# S7CAS-PLEIADES-CARTE-MERE_P02_FPGA_B2B3.net
KiCad netlist of a schematic drawn in Altium Designer
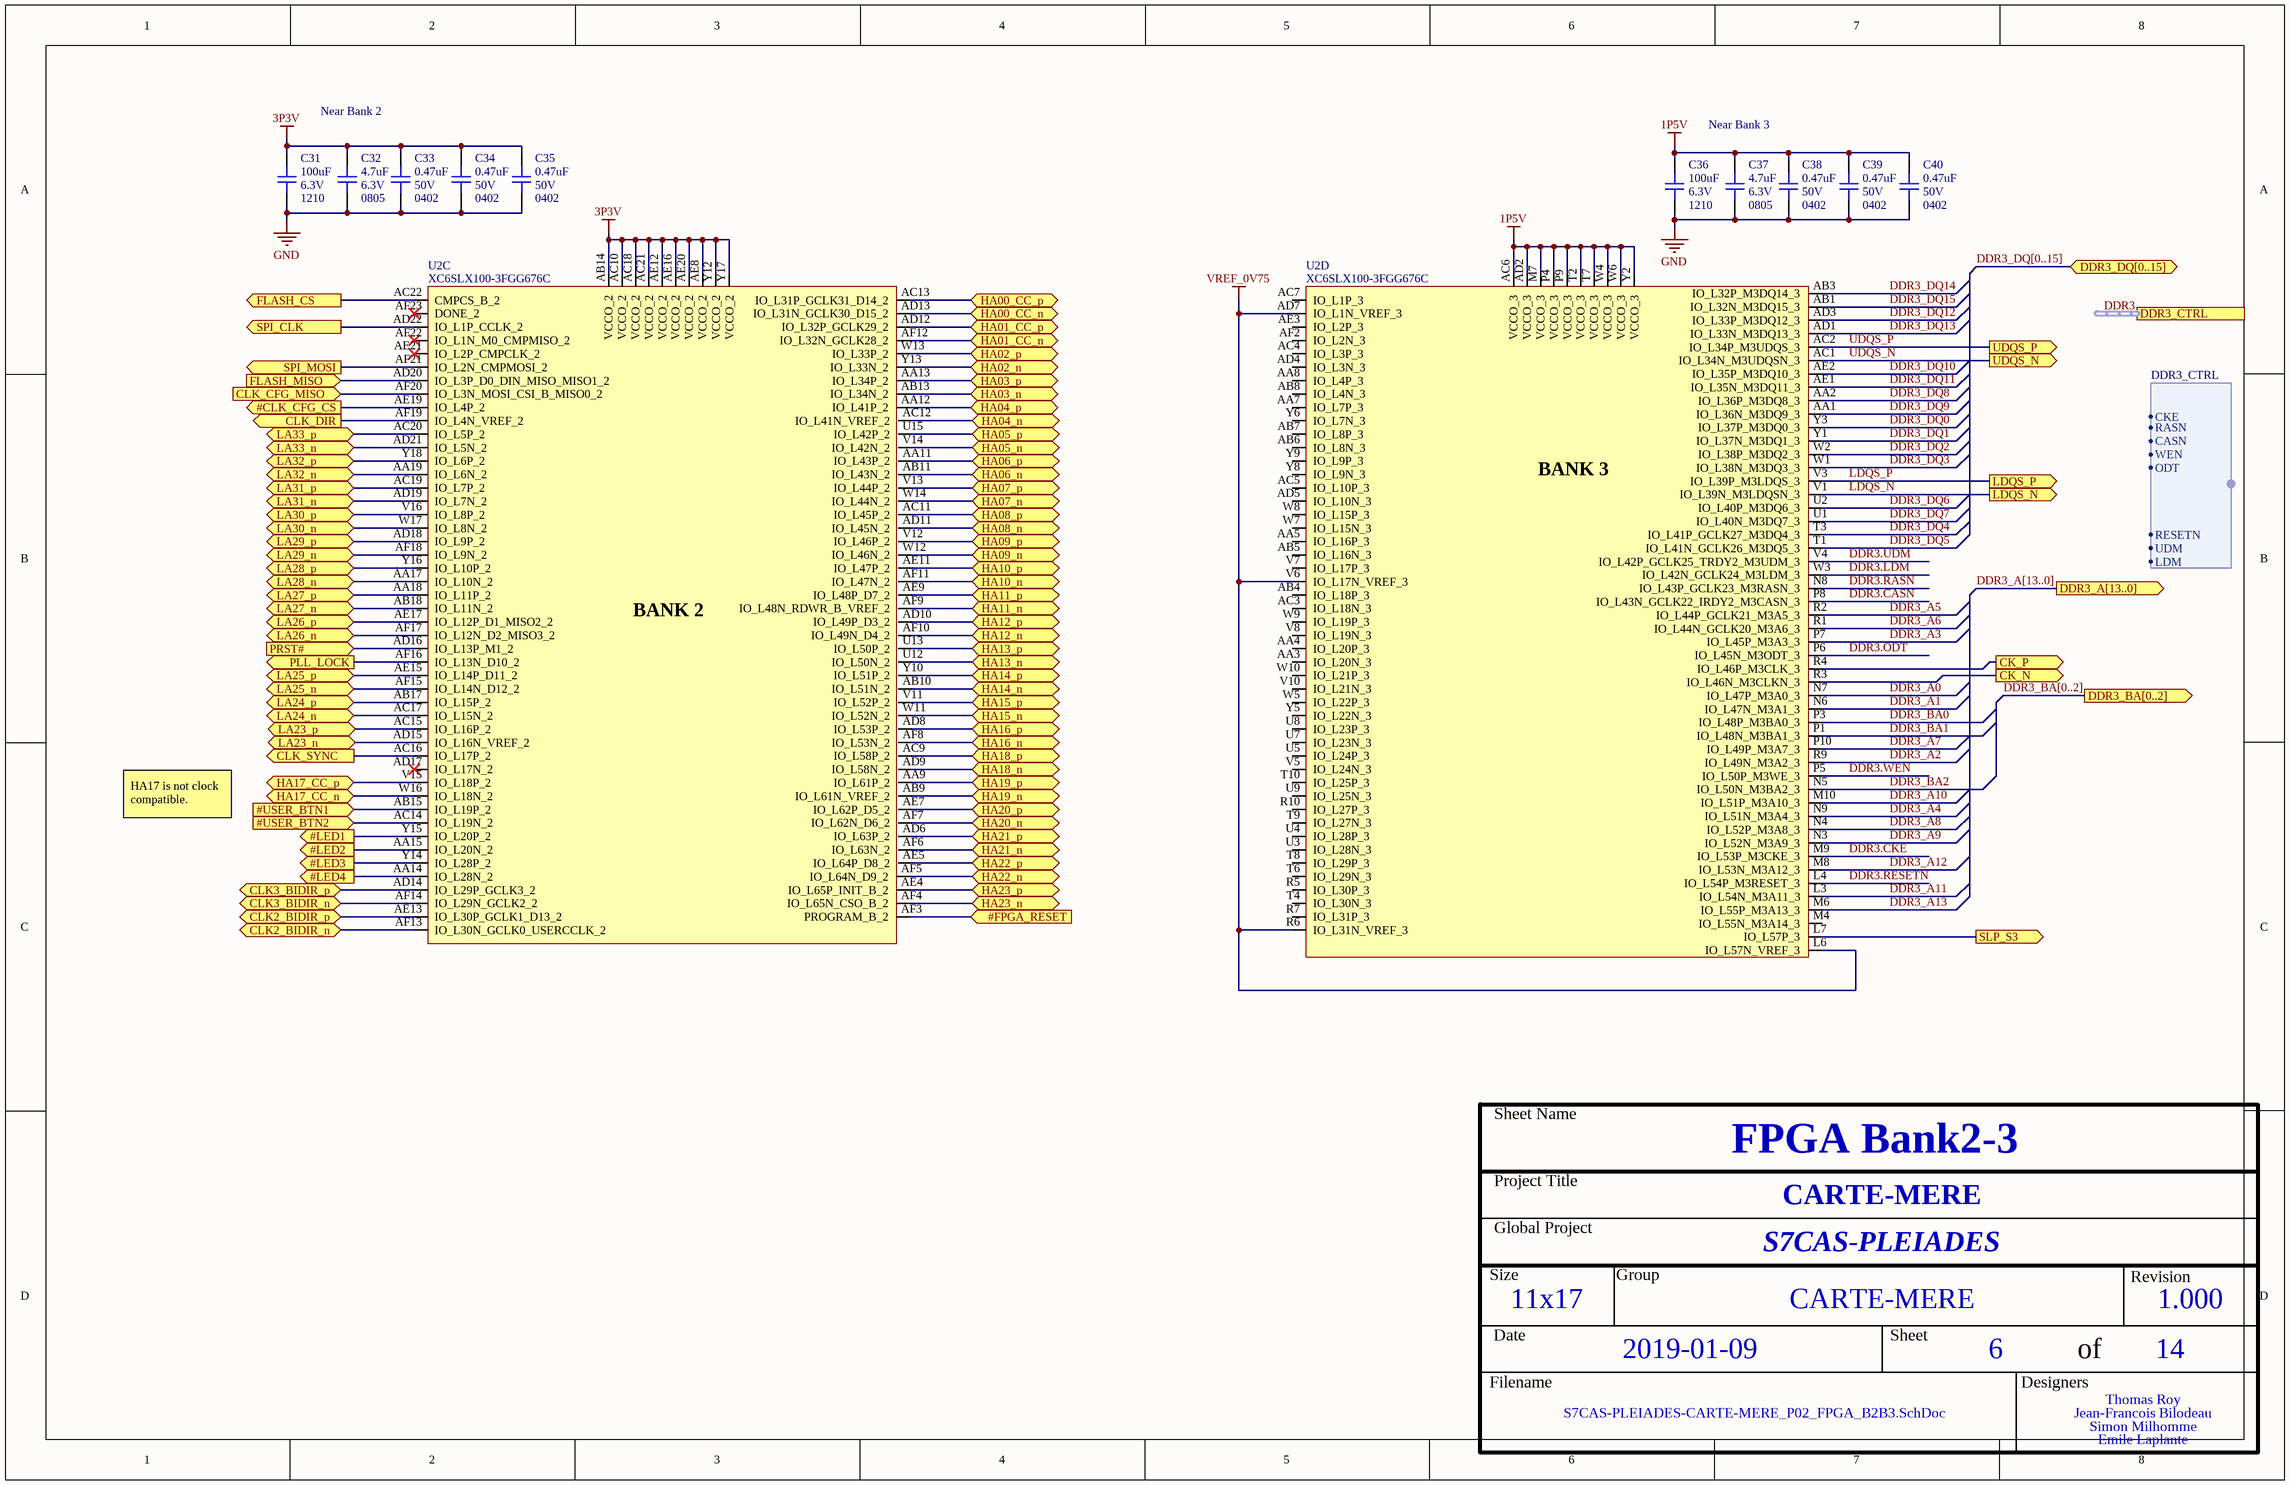
[diagram p0: S7CAS-PLEIADES-CARTE-MERE_P02_FPGA_B2B3.SchDoc]

(export (version "E")
  (design (tool "Eeschema 10.0.6"))
  (components
    (comp (ref "C31")
      (value "100uF")
      (footprint "CAP_1210")
      (description "CAP - 1210")
      (fields
        (field (name "VOLTAGE") "6.3V")
        (field (name "PACKAGE") "1210")
        (field (name "CREATEDBY") "Jonathan Bouchard")
      )
      (libsource (lib "S7CAS_Lib2019_REV1_00") (part "CAP - 1210"))
    )
    (comp (ref "C32")
      (value "4.7uF")
      (footprint "CAP_0805")
      (description "CAP - 0805")
      (fields
        (field (name "VOLTAGE") "6.3V")
        (field (name "PACKAGE") "0805")
        (field (name "CREATEDBY") "Jonathan Bouchard")
      )
      (libsource (lib "S7CAS_Lib2019_REV1_00") (part "CAP - 0805"))
    )
    (comp (ref "C33")
      (value "0.47uF")
      (footprint "CAP_0402")
      (description "CAP - 0402")
      (fields
        (field (name "VOLTAGE") "50V")
        (field (name "PACKAGE") "0402")
        (field (name "CREATEDBY") "Jonathan Bouchard")
      )
      (libsource (lib "S7CAS_Lib2019_REV1_00") (part "CAP - 0402"))
    )
    (comp (ref "C34")
      (value "0.47uF")
      (footprint "CAP_0402")
      (description "CAP - 0402")
      (fields
        (field (name "VOLTAGE") "50V")
        (field (name "PACKAGE") "0402")
        (field (name "CREATEDBY") "Jonathan Bouchard")
      )
      (libsource (lib "S7CAS_Lib2019_REV1_00") (part "CAP - 0402"))
    )
    (comp (ref "C35")
      (value "0.47uF")
      (footprint "CAP_0402")
      (description "CAP - 0402")
      (fields
        (field (name "VOLTAGE") "50V")
        (field (name "PACKAGE") "0402")
        (field (name "CREATEDBY") "Jonathan Bouchard")
      )
      (libsource (lib "S7CAS_Lib2019_REV1_00") (part "CAP - 0402"))
    )
    (comp (ref "C36")
      (value "100uF")
      (footprint "CAP_1210")
      (description "CAP - 1210")
      (fields
        (field (name "VOLTAGE") "6.3V")
        (field (name "PACKAGE") "1210")
        (field (name "CREATEDBY") "Jonathan Bouchard")
      )
      (libsource (lib "S7CAS_Lib2019_REV1_00") (part "CAP - 1210"))
    )
    (comp (ref "C37")
      (value "4.7uF")
      (footprint "CAP_0805")
      (description "CAP - 0805")
      (fields
        (field (name "VOLTAGE") "6.3V")
        (field (name "PACKAGE") "0805")
        (field (name "CREATEDBY") "Jonathan Bouchard")
      )
      (libsource (lib "S7CAS_Lib2019_REV1_00") (part "CAP - 0805"))
    )
    (comp (ref "C38")
      (value "0.47uF")
      (footprint "CAP_0402")
      (description "CAP - 0402")
      (fields
        (field (name "VOLTAGE") "50V")
        (field (name "PACKAGE") "0402")
        (field (name "CREATEDBY") "Jonathan Bouchard")
      )
      (libsource (lib "S7CAS_Lib2019_REV1_00") (part "CAP - 0402"))
    )
    (comp (ref "C39")
      (value "0.47uF")
      (footprint "CAP_0402")
      (description "CAP - 0402")
      (fields
        (field (name "VOLTAGE") "50V")
        (field (name "PACKAGE") "0402")
        (field (name "CREATEDBY") "Jonathan Bouchard")
      )
      (libsource (lib "S7CAS_Lib2019_REV1_00") (part "CAP - 0402"))
    )
    (comp (ref "C40")
      (value "0.47uF")
      (footprint "CAP_0402")
      (description "CAP - 0402")
      (fields
        (field (name "VOLTAGE") "50V")
        (field (name "PACKAGE") "0402")
        (field (name "CREATEDBY") "Jonathan Bouchard")
      )
      (libsource (lib "S7CAS_Lib2019_REV1_00") (part "CAP - 0402"))
    )
    (comp (ref "U2")
      (value "XC6SLX100-3FGG676C")
      (footprint "FPGA_XILINX_FGG676")
      (description "FPGA - XILINX SPARTAN 6 480 I/O - BGA-676")
      (fields
        (field (name "VOLTAGE") "1.14 V ~ 1.26 V")
        (field (name "MFG") "Xilinx")
        (field (name "CREATEDBY") "Jonathan Bouchard")
      )
      (libsource (lib "S7CAS_Lib2019_REV1_00") (part "FPGA_XC6SLX100-3FGG676C"))
    )
  )
  (nets
    (net (code "2") (name "/#CLK_CFG_CS") (class "Default")
      (node (ref "U2") (pin "AE19") (pinfunction "IO_L4P_2_AE19") (pintype "passive"))
    )
    (net (code "3") (name "/#FPGA_RESET") (class "Default")
      (node (ref "U2") (pin "AF3") (pinfunction "PROGRAM_B_2_AF3") (pintype "passive"))
    )
    (net (code "4") (name "/#LED1") (class "Default")
      (node (ref "U2") (pin "Y15") (pinfunction "IO_L20P_2_Y15") (pintype "passive"))
    )
    (net (code "5") (name "/#LED2") (class "Default")
      (node (ref "U2") (pin "AA15") (pinfunction "IO_L20N_2_AA15") (pintype "passive"))
    )
    (net (code "6") (name "/#LED3") (class "Default")
      (node (ref "U2") (pin "Y14") (pinfunction "IO_L28P_2_Y14") (pintype "passive"))
    )
    (net (code "7") (name "/#LED4") (class "Default")
      (node (ref "U2") (pin "AA14") (pinfunction "IO_L28N_2_AA14") (pintype "passive"))
    )
    (net (code "8") (name "/#USER_BTN1") (class "Default")
      (node (ref "U2") (pin "AB15") (pinfunction "IO_L19P_2_AB15") (pintype "passive"))
    )
    (net (code "9") (name "/#USER_BTN2") (class "Default")
      (node (ref "U2") (pin "AC14") (pinfunction "IO_L19N_2_AC14") (pintype "passive"))
    )
    (net (code "10") (name "/CK_N") (class "Default")
      (node (ref "U2") (pin "R3") (pinfunction "IO_L46N_M3CLKN_3_R3") (pintype "passive"))
    )
    (net (code "11") (name "/CK_P") (class "Default")
      (node (ref "U2") (pin "R4") (pinfunction "IO_L46P_M3CLK_3_R4") (pintype "passive"))
    )
    (net (code "12") (name "/CLK2_BIDIR_n") (class "Default")
      (node (ref "U2") (pin "AF13") (pinfunction "IO_L30N_GCLK0_USERCCLK_2_AF13") (pintype "passive"))
    )
    (net (code "13") (name "/CLK2_BIDIR_p") (class "Default")
      (node (ref "U2") (pin "AE13") (pinfunction "IO_L30P_GCLK1_D13_2_AE13") (pintype "passive"))
    )
    (net (code "14") (name "/CLK3_BIDIR_n") (class "Default")
      (node (ref "U2") (pin "AF14") (pinfunction "IO_L29N_GCLK2_2_AF14") (pintype "passive"))
    )
    (net (code "15") (name "/CLK3_BIDIR_p") (class "Default")
      (node (ref "U2") (pin "AD14") (pinfunction "IO_L29P_GCLK3_2_AD14") (pintype "passive"))
    )
    (net (code "16") (name "/CLK_CFG_MISO") (class "Default")
      (node (ref "U2") (pin "AF20") (pinfunction "IO_L3N_MOSI_CSI_B_MISO0_2_AF20") (pintype "passive"))
    )
    (net (code "17") (name "/CLK_DIR") (class "Default")
      (node (ref "U2") (pin "AF19") (pinfunction "IO_L4N_VREF_2_AF19") (pintype "passive"))
    )
    (net (code "18") (name "/CLK_SYNC") (class "Default")
      (node (ref "U2") (pin "AC16") (pinfunction "IO_L17P_2_AC16") (pintype "passive"))
    )
    (net (code "19") (name "/DDR3.CASN") (class "Default")
      (node (ref "U2") (pin "P8") (pinfunction "IO_L43N_GCLK22_IRDY2_M3CASN_3_P8") (pintype "passive"))
    )
    (net (code "20") (name "/DDR3.CKE") (class "Default")
      (node (ref "U2") (pin "M9") (pinfunction "IO_L53P_M3CKE_3_M9") (pintype "passive"))
    )
    (net (code "21") (name "/DDR3.LDM") (class "Default")
      (node (ref "U2") (pin "W3") (pinfunction "IO_L42N_GCLK24_M3LDM_3_W3") (pintype "passive"))
    )
    (net (code "22") (name "/DDR3.ODT") (class "Default")
      (node (ref "U2") (pin "P6") (pinfunction "IO_L45N_M3ODT_3_P6") (pintype "passive"))
    )
    (net (code "23") (name "/DDR3.RASN") (class "Default")
      (node (ref "U2") (pin "N8") (pinfunction "IO_L43P_GCLK23_M3RASN_3_N8") (pintype "passive"))
    )
    (net (code "24") (name "/DDR3.RESETN") (class "Default")
      (node (ref "U2") (pin "L4") (pinfunction "IO_L54P_M3RESET_3_L4") (pintype "passive"))
    )
    (net (code "25") (name "/DDR3.UDM") (class "Default")
      (node (ref "U2") (pin "V4") (pinfunction "IO_L42P_GCLK25_TRDY2_M3UDM_3_V4") (pintype "passive"))
    )
    (net (code "26") (name "/DDR3.WEN") (class "Default")
      (node (ref "U2") (pin "P5") (pinfunction "IO_L50P_M3WE_3_P5") (pintype "passive"))
    )
    (net (code "27") (name "/DDR3_A0") (class "Default")
      (node (ref "U2") (pin "N7") (pinfunction "IO_L47P_M3A0_3_N7") (pintype "passive"))
    )
    (net (code "28") (name "/DDR3_A1") (class "Default")
      (node (ref "U2") (pin "N6") (pinfunction "IO_L47N_M3A1_3_N6") (pintype "passive"))
    )
    (net (code "29") (name "/DDR3_A2") (class "Default")
      (node (ref "U2") (pin "R9") (pinfunction "IO_L49N_M3A2_3_R9") (pintype "passive"))
    )
    (net (code "30") (name "/DDR3_A3") (class "Default")
      (node (ref "U2") (pin "P7") (pinfunction "IO_L45P_M3A3_3_P7") (pintype "passive"))
    )
    (net (code "31") (name "/DDR3_A4") (class "Default")
      (node (ref "U2") (pin "N9") (pinfunction "IO_L51N_M3A4_3_N9") (pintype "passive"))
    )
    (net (code "32") (name "/DDR3_A5") (class "Default")
      (node (ref "U2") (pin "R2") (pinfunction "IO_L44P_GCLK21_M3A5_3_R2") (pintype "passive"))
    )
    (net (code "33") (name "/DDR3_A6") (class "Default")
      (node (ref "U2") (pin "R1") (pinfunction "IO_L44N_GCLK20_M3A6_3_R1") (pintype "passive"))
    )
    (net (code "34") (name "/DDR3_A7") (class "Default")
      (node (ref "U2") (pin "P10") (pinfunction "IO_L49P_M3A7_3_P10") (pintype "passive"))
    )
    (net (code "35") (name "/DDR3_A8") (class "Default")
      (node (ref "U2") (pin "N4") (pinfunction "IO_L52P_M3A8_3_N4") (pintype "passive"))
    )
    (net (code "36") (name "/DDR3_A9") (class "Default")
      (node (ref "U2") (pin "N3") (pinfunction "IO_L52N_M3A9_3_N3") (pintype "passive"))
    )
    (net (code "37") (name "/DDR3_A10") (class "Default")
      (node (ref "U2") (pin "M10") (pinfunction "IO_L51P_M3A10_3_M10") (pintype "passive"))
    )
    (net (code "38") (name "/DDR3_A11") (class "Default")
      (node (ref "U2") (pin "L3") (pinfunction "IO_L54N_M3A11_3_L3") (pintype "passive"))
    )
    (net (code "39") (name "/DDR3_A12") (class "Default")
      (node (ref "U2") (pin "M8") (pinfunction "IO_L53N_M3A12_3_M8") (pintype "passive"))
    )
    (net (code "40") (name "/DDR3_A13") (class "Default")
      (node (ref "U2") (pin "M6") (pinfunction "IO_L55P_M3A13_3_M6") (pintype "passive"))
    )
    (net (code "42") (name "/DDR3_BA0") (class "Default")
      (node (ref "U2") (pin "P3") (pinfunction "IO_L48P_M3BA0_3_P3") (pintype "passive"))
    )
    (net (code "43") (name "/DDR3_BA1") (class "Default")
      (node (ref "U2") (pin "P1") (pinfunction "IO_L48N_M3BA1_3_P1") (pintype "passive"))
    )
    (net (code "44") (name "/DDR3_BA2") (class "Default")
      (node (ref "U2") (pin "N5") (pinfunction "IO_L50N_M3BA2_3_N5") (pintype "passive"))
    )
    (net (code "46") (name "/DDR3_DQ0") (class "Default")
      (node (ref "U2") (pin "Y3") (pinfunction "IO_L37P_M3DQ0_3_Y3") (pintype "passive"))
    )
    (net (code "47") (name "/DDR3_DQ1") (class "Default")
      (node (ref "U2") (pin "Y1") (pinfunction "IO_L37N_M3DQ1_3_Y1") (pintype "passive"))
    )
    (net (code "48") (name "/DDR3_DQ2") (class "Default")
      (node (ref "U2") (pin "W2") (pinfunction "IO_L38P_M3DQ2_3_W2") (pintype "passive"))
    )
    (net (code "49") (name "/DDR3_DQ3") (class "Default")
      (node (ref "U2") (pin "W1") (pinfunction "IO_L38N_M3DQ3_3_W1") (pintype "passive"))
    )
    (net (code "50") (name "/DDR3_DQ4") (class "Default")
      (node (ref "U2") (pin "T3") (pinfunction "IO_L41P_GCLK27_M3DQ4_3_T3") (pintype "passive"))
    )
    (net (code "51") (name "/DDR3_DQ5") (class "Default")
      (node (ref "U2") (pin "T1") (pinfunction "IO_L41N_GCLK26_M3DQ5_3_T1") (pintype "passive"))
    )
    (net (code "52") (name "/DDR3_DQ6") (class "Default")
      (node (ref "U2") (pin "U2") (pinfunction "IO_L40P_M3DQ6_3_U2") (pintype "passive"))
    )
    (net (code "53") (name "/DDR3_DQ7") (class "Default")
      (node (ref "U2") (pin "U1") (pinfunction "IO_L40N_M3DQ7_3_U1") (pintype "passive"))
    )
    (net (code "54") (name "/DDR3_DQ8") (class "Default")
      (node (ref "U2") (pin "AA2") (pinfunction "IO_L36P_M3DQ8_3_AA2") (pintype "passive"))
    )
    (net (code "55") (name "/DDR3_DQ9") (class "Default")
      (node (ref "U2") (pin "AA1") (pinfunction "IO_L36N_M3DQ9_3_AA1") (pintype "passive"))
    )
    (net (code "56") (name "/DDR3_DQ10") (class "Default")
      (node (ref "U2") (pin "AE2") (pinfunction "IO_L35P_M3DQ10_3_AE2") (pintype "passive"))
    )
    (net (code "57") (name "/DDR3_DQ11") (class "Default")
      (node (ref "U2") (pin "AE1") (pinfunction "IO_L35N_M3DQ11_3_AE1") (pintype "passive"))
    )
    (net (code "58") (name "/DDR3_DQ12") (class "Default")
      (node (ref "U2") (pin "AD3") (pinfunction "IO_L33P_M3DQ12_3_AD3") (pintype "passive"))
    )
    (net (code "59") (name "/DDR3_DQ13") (class "Default")
      (node (ref "U2") (pin "AD1") (pinfunction "IO_L33N_M3DQ13_3_AD1") (pintype "passive"))
    )
    (net (code "60") (name "/DDR3_DQ14") (class "Default")
      (node (ref "U2") (pin "AB3") (pinfunction "IO_L32P_M3DQ14_3_AB3") (pintype "passive"))
    )
    (net (code "61") (name "/DDR3_DQ15") (class "Default")
      (node (ref "U2") (pin "AB1") (pinfunction "IO_L32N_M3DQ15_3_AB1") (pintype "passive"))
    )
    (net (code "63") (name "/FLASH_CS") (class "Default")
      (node (ref "U2") (pin "AC22") (pinfunction "CMPCS_B_2_AC22") (pintype "passive"))
    )
    (net (code "64") (name "/FLASH_MISO") (class "Default")
      (node (ref "U2") (pin "AD20") (pinfunction "IO_L3P_D0_DIN_MISO_MISO1_2_AD20") (pintype "passive"))
    )
    (net (code "65") (name "/HA00_CC_n") (class "Default")
      (node (ref "U2") (pin "AD13") (pinfunction "IO_L31N_GCLK30_D15_2_AD13") (pintype "passive"))
    )
    (net (code "66") (name "/HA00_CC_p") (class "Default")
      (node (ref "U2") (pin "AC13") (pinfunction "IO_L31P_GCLK31_D14_2_AC13") (pintype "passive"))
    )
    (net (code "67") (name "/HA01_CC_n") (class "Default")
      (node (ref "U2") (pin "AF12") (pinfunction "IO_L32N_GCLK28_2_AF12") (pintype "passive"))
    )
    (net (code "68") (name "/HA01_CC_p") (class "Default")
      (node (ref "U2") (pin "AD12") (pinfunction "IO_L32P_GCLK29_2_AD12") (pintype "passive"))
    )
    (net (code "69") (name "/HA02_n") (class "Default")
      (node (ref "U2") (pin "Y13") (pinfunction "IO_L33N_2_Y13") (pintype "passive"))
    )
    (net (code "70") (name "/HA02_p") (class "Default")
      (node (ref "U2") (pin "W13") (pinfunction "IO_L33P_2_W13") (pintype "passive"))
    )
    (net (code "71") (name "/HA03_n") (class "Default")
      (node (ref "U2") (pin "AB13") (pinfunction "IO_L34N_2_AB13") (pintype "passive"))
    )
    (net (code "72") (name "/HA03_p") (class "Default")
      (node (ref "U2") (pin "AA13") (pinfunction "IO_L34P_2_AA13") (pintype "passive"))
    )
    (net (code "73") (name "/HA04_n") (class "Default")
      (node (ref "U2") (pin "AC12") (pinfunction "IO_L41N_VREF_2_AC12") (pintype "passive"))
    )
    (net (code "74") (name "/HA04_p") (class "Default")
      (node (ref "U2") (pin "AA12") (pinfunction "IO_L41P_2_AA12") (pintype "passive"))
    )
    (net (code "75") (name "/HA05_n") (class "Default")
      (node (ref "U2") (pin "V14") (pinfunction "IO_L42N_2_V14") (pintype "passive"))
    )
    (net (code "76") (name "/HA05_p") (class "Default")
      (node (ref "U2") (pin "U15") (pinfunction "IO_L42P_2_U15") (pintype "passive"))
    )
    (net (code "77") (name "/HA06_n") (class "Default")
      (node (ref "U2") (pin "AB11") (pinfunction "IO_L43N_2_AB11") (pintype "passive"))
    )
    (net (code "78") (name "/HA06_p") (class "Default")
      (node (ref "U2") (pin "AA11") (pinfunction "IO_L43P_2_AA11") (pintype "passive"))
    )
    (net (code "79") (name "/HA07_n") (class "Default")
      (node (ref "U2") (pin "W14") (pinfunction "IO_L44N_2_W14") (pintype "passive"))
    )
    (net (code "80") (name "/HA07_p") (class "Default")
      (node (ref "U2") (pin "V13") (pinfunction "IO_L44P_2_V13") (pintype "passive"))
    )
    (net (code "81") (name "/HA08_n") (class "Default")
      (node (ref "U2") (pin "AD11") (pinfunction "IO_L45N_2_AD11") (pintype "passive"))
    )
    (net (code "82") (name "/HA08_p") (class "Default")
      (node (ref "U2") (pin "AC11") (pinfunction "IO_L45P_2_AC11") (pintype "passive"))
    )
    (net (code "83") (name "/HA09_n") (class "Default")
      (node (ref "U2") (pin "W12") (pinfunction "IO_L46N_2_W12") (pintype "passive"))
    )
    (net (code "84") (name "/HA09_p") (class "Default")
      (node (ref "U2") (pin "V12") (pinfunction "IO_L46P_2_V12") (pintype "passive"))
    )
    (net (code "85") (name "/HA10_n") (class "Default")
      (node (ref "U2") (pin "AF11") (pinfunction "IO_L47N_2_AF11") (pintype "passive"))
    )
    (net (code "86") (name "/HA10_p") (class "Default")
      (node (ref "U2") (pin "AE11") (pinfunction "IO_L47P_2_AE11") (pintype "passive"))
    )
    (net (code "87") (name "/HA11_n") (class "Default")
      (node (ref "U2") (pin "AF9") (pinfunction "IO_L48N_RDWR_B_VREF_2_AF9") (pintype "passive"))
    )
    (net (code "88") (name "/HA11_p") (class "Default")
      (node (ref "U2") (pin "AE9") (pinfunction "IO_L48P_D7_2_AE9") (pintype "passive"))
    )
    (net (code "89") (name "/HA12_n") (class "Default")
      (node (ref "U2") (pin "AF10") (pinfunction "IO_L49N_D4_2_AF10") (pintype "passive"))
    )
    (net (code "90") (name "/HA12_p") (class "Default")
      (node (ref "U2") (pin "AD10") (pinfunction "IO_L49P_D3_2_AD10") (pintype "passive"))
    )
    (net (code "91") (name "/HA13_n") (class "Default")
      (node (ref "U2") (pin "U12") (pinfunction "IO_L50N_2_U12") (pintype "passive"))
    )
    (net (code "92") (name "/HA13_p") (class "Default")
      (node (ref "U2") (pin "U13") (pinfunction "IO_L50P_2_U13") (pintype "passive"))
    )
    (net (code "93") (name "/HA14_n") (class "Default")
      (node (ref "U2") (pin "AB10") (pinfunction "IO_L51N_2_AB10") (pintype "passive"))
    )
    (net (code "94") (name "/HA14_p") (class "Default")
      (node (ref "U2") (pin "Y10") (pinfunction "IO_L51P_2_Y10") (pintype "passive"))
    )
    (net (code "95") (name "/HA15_n") (class "Default")
      (node (ref "U2") (pin "W11") (pinfunction "IO_L52N_2_W11") (pintype "passive"))
    )
    (net (code "96") (name "/HA15_p") (class "Default")
      (node (ref "U2") (pin "V11") (pinfunction "IO_L52P_2_V11") (pintype "passive"))
    )
    (net (code "97") (name "/HA16_n") (class "Default")
      (node (ref "U2") (pin "AF8") (pinfunction "IO_L53N_2_AF8") (pintype "passive"))
    )
    (net (code "98") (name "/HA16_p") (class "Default")
      (node (ref "U2") (pin "AD8") (pinfunction "IO_L53P_2_AD8") (pintype "passive"))
    )
    (net (code "99") (name "/HA17_CC_n") (class "Default")
      (node (ref "U2") (pin "W16") (pinfunction "IO_L18N_2_W16") (pintype "passive"))
    )
    (net (code "100") (name "/HA17_CC_p") (class "Default")
      (node (ref "U2") (pin "V15") (pinfunction "IO_L18P_2_V15") (pintype "passive"))
    )
    (net (code "101") (name "/HA18_n") (class "Default")
      (node (ref "U2") (pin "AD9") (pinfunction "IO_L58N_2_AD9") (pintype "passive"))
    )
    (net (code "102") (name "/HA18_p") (class "Default")
      (node (ref "U2") (pin "AC9") (pinfunction "IO_L58P_2_AC9") (pintype "passive"))
    )
    (net (code "103") (name "/HA19_n") (class "Default")
      (node (ref "U2") (pin "AB9") (pinfunction "IO_L61N_VREF_2_AB9") (pintype "passive"))
    )
    (net (code "104") (name "/HA19_p") (class "Default")
      (node (ref "U2") (pin "AA9") (pinfunction "IO_L61P_2_AA9") (pintype "passive"))
    )
    (net (code "105") (name "/HA20_n") (class "Default")
      (node (ref "U2") (pin "AF7") (pinfunction "IO_L62N_D6_2_AF7") (pintype "passive"))
    )
    (net (code "106") (name "/HA20_p") (class "Default")
      (node (ref "U2") (pin "AE7") (pinfunction "IO_L62P_D5_2_AE7") (pintype "passive"))
    )
    (net (code "107") (name "/HA21_n") (class "Default")
      (node (ref "U2") (pin "AF6") (pinfunction "IO_L63N_2_AF6") (pintype "passive"))
    )
    (net (code "108") (name "/HA21_p") (class "Default")
      (node (ref "U2") (pin "AD6") (pinfunction "IO_L63P_2_AD6") (pintype "passive"))
    )
    (net (code "109") (name "/HA22_n") (class "Default")
      (node (ref "U2") (pin "AF5") (pinfunction "IO_L64N_D9_2_AF5") (pintype "passive"))
    )
    (net (code "110") (name "/HA22_p") (class "Default")
      (node (ref "U2") (pin "AE5") (pinfunction "IO_L64P_D8_2_AE5") (pintype "passive"))
    )
    (net (code "111") (name "/HA23_n") (class "Default")
      (node (ref "U2") (pin "AF4") (pinfunction "IO_L65N_CSO_B_2_AF4") (pintype "passive"))
    )
    (net (code "112") (name "/HA23_p") (class "Default")
      (node (ref "U2") (pin "AE4") (pinfunction "IO_L65P_INIT_B_2_AE4") (pintype "passive"))
    )
    (net (code "113") (name "/LA23_n") (class "Default")
      (node (ref "U2") (pin "AD15") (pinfunction "IO_L16N_VREF_2_AD15") (pintype "passive"))
    )
    (net (code "114") (name "/LA23_p") (class "Default")
      (node (ref "U2") (pin "AC15") (pinfunction "IO_L16P_2_AC15") (pintype "passive"))
    )
    (net (code "115") (name "/LA24_n") (class "Default")
      (node (ref "U2") (pin "AC17") (pinfunction "IO_L15N_2_AC17") (pintype "passive"))
    )
    (net (code "116") (name "/LA24_p") (class "Default")
      (node (ref "U2") (pin "AB17") (pinfunction "IO_L15P_2_AB17") (pintype "passive"))
    )
    (net (code "117") (name "/LA25_n") (class "Default")
      (node (ref "U2") (pin "AF15") (pinfunction "IO_L14N_D12_2_AF15") (pintype "passive"))
    )
    (net (code "118") (name "/LA25_p") (class "Default")
      (node (ref "U2") (pin "AE15") (pinfunction "IO_L14P_D11_2_AE15") (pintype "passive"))
    )
    (net (code "119") (name "/LA26_n") (class "Default")
      (node (ref "U2") (pin "AF17") (pinfunction "IO_L12N_D2_MISO3_2_AF17") (pintype "passive"))
    )
    (net (code "120") (name "/LA26_p") (class "Default")
      (node (ref "U2") (pin "AE17") (pinfunction "IO_L12P_D1_MISO2_2_AE17") (pintype "passive"))
    )
    (net (code "121") (name "/LA27_n") (class "Default")
      (node (ref "U2") (pin "AB18") (pinfunction "IO_L11N_2_AB18") (pintype "passive"))
    )
    (net (code "122") (name "/LA27_p") (class "Default")
      (node (ref "U2") (pin "AA18") (pinfunction "IO_L11P_2_AA18") (pintype "passive"))
    )
    (net (code "123") (name "/LA28_n") (class "Default")
      (node (ref "U2") (pin "AA17") (pinfunction "IO_L10N_2_AA17") (pintype "passive"))
    )
    (net (code "124") (name "/LA28_p") (class "Default")
      (node (ref "U2") (pin "Y16") (pinfunction "IO_L10P_2_Y16") (pintype "passive"))
    )
    (net (code "125") (name "/LA29_n") (class "Default")
      (node (ref "U2") (pin "AF18") (pinfunction "IO_L9N_2_AF18") (pintype "passive"))
    )
    (net (code "126") (name "/LA29_p") (class "Default")
      (node (ref "U2") (pin "AD18") (pinfunction "IO_L9P_2_AD18") (pintype "passive"))
    )
    (net (code "127") (name "/LA30_n") (class "Default")
      (node (ref "U2") (pin "W17") (pinfunction "IO_L8N_2_W17") (pintype "passive"))
    )
    (net (code "128") (name "/LA30_p") (class "Default")
      (node (ref "U2") (pin "V16") (pinfunction "IO_L8P_2_V16") (pintype "passive"))
    )
    (net (code "129") (name "/LA31_n") (class "Default")
      (node (ref "U2") (pin "AD19") (pinfunction "IO_L7N_2_AD19") (pintype "passive"))
    )
    (net (code "130") (name "/LA31_p") (class "Default")
      (node (ref "U2") (pin "AC19") (pinfunction "IO_L7P_2_AC19") (pintype "passive"))
    )
    (net (code "131") (name "/LA32_n") (class "Default")
      (node (ref "U2") (pin "AA19") (pinfunction "IO_L6N_2_AA19") (pintype "passive"))
    )
    (net (code "132") (name "/LA32_p") (class "Default")
      (node (ref "U2") (pin "Y18") (pinfunction "IO_L6P_2_Y18") (pintype "passive"))
    )
    (net (code "133") (name "/LA33_n") (class "Default")
      (node (ref "U2") (pin "AD21") (pinfunction "IO_L5N_2_AD21") (pintype "passive"))
    )
    (net (code "134") (name "/LA33_p") (class "Default")
      (node (ref "U2") (pin "AC20") (pinfunction "IO_L5P_2_AC20") (pintype "passive"))
    )
    (net (code "135") (name "/LDQS_N") (class "Default")
      (node (ref "U2") (pin "V1") (pinfunction "IO_L39N_M3LDQSN_3_V1") (pintype "passive"))
    )
    (net (code "136") (name "/LDQS_P") (class "Default")
      (node (ref "U2") (pin "V3") (pinfunction "IO_L39P_M3LDQS_3_V3") (pintype "passive"))
    )
    (net (code "137") (name "/PLL_LOCK") (class "Default")
      (node (ref "U2") (pin "AF16") (pinfunction "IO_L13N_D10_2_AF16") (pintype "passive"))
    )
    (net (code "138") (name "/PRST#") (class "Default")
      (node (ref "U2") (pin "AD16") (pinfunction "IO_L13P_M1_2_AD16") (pintype "passive"))
    )
    (net (code "139") (name "/SLP_S3") (class "Default")
      (node (ref "U2") (pin "L7") (pinfunction "IO_L57P_3_L7") (pintype "passive"))
    )
    (net (code "140") (name "/SPI_CLK") (class "Default")
      (node (ref "U2") (pin "AD22") (pinfunction "IO_L1P_CCLK_2_AD22") (pintype "passive"))
    )
    (net (code "141") (name "/SPI_MOSI") (class "Default")
      (node (ref "U2") (pin "AF21") (pinfunction "IO_L2N_CMPMOSI_2_AF21") (pintype "passive"))
    )
    (net (code "142") (name "/UDQS_N") (class "Default")
      (node (ref "U2") (pin "AC1") (pinfunction "IO_L34N_M3UDQSN_3_AC1") (pintype "passive"))
    )
    (net (code "143") (name "/UDQS_P") (class "Default")
      (node (ref "U2") (pin "AC2") (pinfunction "IO_L34P_M3UDQS_3_AC2") (pintype "passive"))
    )
    (net (code "145") (name "1P5V") (class "Default")
      (node (ref "C36") (pin "2") (pinfunction "2_2") (pintype "passive"))
      (node (ref "C37") (pin "2") (pinfunction "2_2") (pintype "passive"))
      (node (ref "C38") (pin "2") (pinfunction "2_2") (pintype "passive"))
      (node (ref "C39") (pin "2") (pinfunction "2_2") (pintype "passive"))
      (node (ref "C40") (pin "2") (pinfunction "2_2") (pintype "passive"))
      (node (ref "U2") (pin "AC6") (pinfunction "VCCO_3_AC6") (pintype "passive"))
      (node (ref "U2") (pin "AD2") (pinfunction "VCCO_3_AD2") (pintype "passive"))
      (node (ref "U2") (pin "M7") (pinfunction "VCCO_3_M7") (pintype "passive"))
      (node (ref "U2") (pin "P4") (pinfunction "VCCO_3_P4") (pintype "passive"))
      (node (ref "U2") (pin "P9") (pinfunction "VCCO_3_P9") (pintype "passive"))
      (node (ref "U2") (pin "T2") (pinfunction "VCCO_3_T2") (pintype "passive"))
      (node (ref "U2") (pin "T7") (pinfunction "VCCO_3_T7") (pintype "passive"))
      (node (ref "U2") (pin "W4") (pinfunction "VCCO_3_W4") (pintype "passive"))
      (node (ref "U2") (pin "W6") (pinfunction "VCCO_3_W6") (pintype "passive"))
      (node (ref "U2") (pin "Y2") (pinfunction "VCCO_3_Y2") (pintype "passive"))
    )
    (net (code "146") (name "3P3V") (class "Default")
      (node (ref "C31") (pin "2") (pinfunction "2_2") (pintype "passive"))
      (node (ref "C32") (pin "2") (pinfunction "2_2") (pintype "passive"))
      (node (ref "C33") (pin "2") (pinfunction "2_2") (pintype "passive"))
      (node (ref "C34") (pin "2") (pinfunction "2_2") (pintype "passive"))
      (node (ref "C35") (pin "2") (pinfunction "2_2") (pintype "passive"))
      (node (ref "U2") (pin "AB14") (pinfunction "VCCO_2_AB14") (pintype "passive"))
      (node (ref "U2") (pin "AC10") (pinfunction "VCCO_2_AC10") (pintype "passive"))
      (node (ref "U2") (pin "AC18") (pinfunction "VCCO_2_AC18") (pintype "passive"))
      (node (ref "U2") (pin "AC21") (pinfunction "VCCO_2_AC21") (pintype "passive"))
      (node (ref "U2") (pin "AE12") (pinfunction "VCCO_2_AE12") (pintype "passive"))
      (node (ref "U2") (pin "AE16") (pinfunction "VCCO_2_AE16") (pintype "passive"))
      (node (ref "U2") (pin "AE20") (pinfunction "VCCO_2_AE20") (pintype "passive"))
      (node (ref "U2") (pin "AE8") (pinfunction "VCCO_2_AE8") (pintype "passive"))
      (node (ref "U2") (pin "Y12") (pinfunction "VCCO_2_Y12") (pintype "passive"))
      (node (ref "U2") (pin "Y17") (pinfunction "VCCO_2_Y17") (pintype "passive"))
    )
    (net (code "147") (name "GND") (class "Default")
      (node (ref "C31") (pin "1") (pinfunction "1_1") (pintype "passive"))
      (node (ref "C32") (pin "1") (pinfunction "1_1") (pintype "passive"))
      (node (ref "C33") (pin "1") (pinfunction "1_1") (pintype "passive"))
      (node (ref "C34") (pin "1") (pinfunction "1_1") (pintype "passive"))
      (node (ref "C35") (pin "1") (pinfunction "1_1") (pintype "passive"))
      (node (ref "C36") (pin "1") (pinfunction "1_1") (pintype "passive"))
      (node (ref "C37") (pin "1") (pinfunction "1_1") (pintype "passive"))
      (node (ref "C38") (pin "1") (pinfunction "1_1") (pintype "passive"))
      (node (ref "C39") (pin "1") (pinfunction "1_1") (pintype "passive"))
      (node (ref "C40") (pin "1") (pinfunction "1_1") (pintype "passive"))
    )
    (net (code "148") (name "VREF_0V75") (class "Default")
      (node (ref "U2") (pin "AD7") (pinfunction "IO_L1N_VREF_3_AD7") (pintype "passive"))
      (node (ref "U2") (pin "L6") (pinfunction "IO_L57N_VREF_3_L6") (pintype "passive"))
      (node (ref "U2") (pin "R6") (pinfunction "IO_L31N_VREF_3_R6") (pintype "passive"))
      (node (ref "U2") (pin "V6") (pinfunction "IO_L17N_VREF_3_V6") (pintype "passive"))
    )
    (net (code "149") (name "unconnected-(U2C-DONE_2-PadAF23)") (class "Default")
      (node (ref "U2") (pin "AF23") (pinfunction "DONE_2_AF23") (pintype "passive+no_connect"))
    )
    (net (code "150") (name "unconnected-(U2C-IO_L1N_M0_CMPMISO_2-PadAF22)") (class "Default")
      (node (ref "U2") (pin "AF22") (pinfunction "IO_L1N_M0_CMPMISO_2_AF22") (pintype "passive+no_connect"))
    )
    (net (code "151") (name "unconnected-(U2C-IO_L2P_CMPCLK_2-PadAE21)") (class "Default")
      (node (ref "U2") (pin "AE21") (pinfunction "IO_L2P_CMPCLK_2_AE21") (pintype "passive+no_connect"))
    )
    (net (code "152") (name "unconnected-(U2C-IO_L17N_2-PadAD17)") (class "Default")
      (node (ref "U2") (pin "AD17") (pinfunction "IO_L17N_2_AD17") (pintype "passive+no_connect"))
    )
    (net (code "153") (name "unconnected-(U2D-IO_L1P_3-PadAC7)") (class "Default")
      (node (ref "U2") (pin "AC7") (pinfunction "IO_L1P_3_AC7") (pintype "passive"))
    )
    (net (code "154") (name "unconnected-(U2D-IO_L2N_3-PadAF2)") (class "Default")
      (node (ref "U2") (pin "AF2") (pinfunction "IO_L2N_3_AF2") (pintype "passive"))
    )
    (net (code "155") (name "unconnected-(U2D-IO_L2P_3-PadAE3)") (class "Default")
      (node (ref "U2") (pin "AE3") (pinfunction "IO_L2P_3_AE3") (pintype "passive"))
    )
    (net (code "156") (name "unconnected-(U2D-IO_L3N_3-PadAD4)") (class "Default")
      (node (ref "U2") (pin "AD4") (pinfunction "IO_L3N_3_AD4") (pintype "passive"))
    )
    (net (code "157") (name "unconnected-(U2D-IO_L3P_3-PadAC4)") (class "Default")
      (node (ref "U2") (pin "AC4") (pinfunction "IO_L3P_3_AC4") (pintype "passive"))
    )
    (net (code "158") (name "unconnected-(U2D-IO_L4N_3-PadAB8)") (class "Default")
      (node (ref "U2") (pin "AB8") (pinfunction "IO_L4N_3_AB8") (pintype "passive"))
    )
    (net (code "159") (name "unconnected-(U2D-IO_L4P_3-PadAA8)") (class "Default")
      (node (ref "U2") (pin "AA8") (pinfunction "IO_L4P_3_AA8") (pintype "passive"))
    )
    (net (code "160") (name "unconnected-(U2D-IO_L7N_3-PadY6)") (class "Default")
      (node (ref "U2") (pin "Y6") (pinfunction "IO_L7N_3_Y6") (pintype "passive"))
    )
    (net (code "161") (name "unconnected-(U2D-IO_L7P_3-PadAA7)") (class "Default")
      (node (ref "U2") (pin "AA7") (pinfunction "IO_L7P_3_AA7") (pintype "passive"))
    )
    (net (code "162") (name "unconnected-(U2D-IO_L8N_3-PadAB6)") (class "Default")
      (node (ref "U2") (pin "AB6") (pinfunction "IO_L8N_3_AB6") (pintype "passive"))
    )
    (net (code "163") (name "unconnected-(U2D-IO_L8P_3-PadAB7)") (class "Default")
      (node (ref "U2") (pin "AB7") (pinfunction "IO_L8P_3_AB7") (pintype "passive"))
    )
    (net (code "164") (name "unconnected-(U2D-IO_L9N_3-PadY8)") (class "Default")
      (node (ref "U2") (pin "Y8") (pinfunction "IO_L9N_3_Y8") (pintype "passive"))
    )
    (net (code "165") (name "unconnected-(U2D-IO_L9P_3-PadY9)") (class "Default")
      (node (ref "U2") (pin "Y9") (pinfunction "IO_L9P_3_Y9") (pintype "passive"))
    )
    (net (code "166") (name "unconnected-(U2D-IO_L10N_3-PadAD5)") (class "Default")
      (node (ref "U2") (pin "AD5") (pinfunction "IO_L10N_3_AD5") (pintype "passive"))
    )
    (net (code "167") (name "unconnected-(U2D-IO_L10P_3-PadAC5)") (class "Default")
      (node (ref "U2") (pin "AC5") (pinfunction "IO_L10P_3_AC5") (pintype "passive"))
    )
    (net (code "168") (name "unconnected-(U2D-IO_L15N_3-PadW7)") (class "Default")
      (node (ref "U2") (pin "W7") (pinfunction "IO_L15N_3_W7") (pintype "passive"))
    )
    (net (code "169") (name "unconnected-(U2D-IO_L15P_3-PadW8)") (class "Default")
      (node (ref "U2") (pin "W8") (pinfunction "IO_L15P_3_W8") (pintype "passive"))
    )
    (net (code "170") (name "unconnected-(U2D-IO_L16N_3-PadAB5)") (class "Default")
      (node (ref "U2") (pin "AB5") (pinfunction "IO_L16N_3_AB5") (pintype "passive"))
    )
    (net (code "171") (name "unconnected-(U2D-IO_L16P_3-PadAA5)") (class "Default")
      (node (ref "U2") (pin "AA5") (pinfunction "IO_L16P_3_AA5") (pintype "passive"))
    )
    (net (code "172") (name "unconnected-(U2D-IO_L17P_3-PadV7)") (class "Default")
      (node (ref "U2") (pin "V7") (pinfunction "IO_L17P_3_V7") (pintype "passive"))
    )
    (net (code "173") (name "unconnected-(U2D-IO_L18N_3-PadAC3)") (class "Default")
      (node (ref "U2") (pin "AC3") (pinfunction "IO_L18N_3_AC3") (pintype "passive"))
    )
    (net (code "174") (name "unconnected-(U2D-IO_L18P_3-PadAB4)") (class "Default")
      (node (ref "U2") (pin "AB4") (pinfunction "IO_L18P_3_AB4") (pintype "passive"))
    )
    (net (code "175") (name "unconnected-(U2D-IO_L19N_3-PadV8)") (class "Default")
      (node (ref "U2") (pin "V8") (pinfunction "IO_L19N_3_V8") (pintype "passive"))
    )
    (net (code "176") (name "unconnected-(U2D-IO_L19P_3-PadW9)") (class "Default")
      (node (ref "U2") (pin "W9") (pinfunction "IO_L19P_3_W9") (pintype "passive"))
    )
    (net (code "177") (name "unconnected-(U2D-IO_L20N_3-PadAA3)") (class "Default")
      (node (ref "U2") (pin "AA3") (pinfunction "IO_L20N_3_AA3") (pintype "passive"))
    )
    (net (code "178") (name "unconnected-(U2D-IO_L20P_3-PadAA4)") (class "Default")
      (node (ref "U2") (pin "AA4") (pinfunction "IO_L20P_3_AA4") (pintype "passive"))
    )
    (net (code "179") (name "unconnected-(U2D-IO_L21N_3-PadV10)") (class "Default")
      (node (ref "U2") (pin "V10") (pinfunction "IO_L21N_3_V10") (pintype "passive"))
    )
    (net (code "180") (name "unconnected-(U2D-IO_L21P_3-PadW10)") (class "Default")
      (node (ref "U2") (pin "W10") (pinfunction "IO_L21P_3_W10") (pintype "passive"))
    )
    (net (code "181") (name "unconnected-(U2D-IO_L22N_3-PadY5)") (class "Default")
      (node (ref "U2") (pin "Y5") (pinfunction "IO_L22N_3_Y5") (pintype "passive"))
    )
    (net (code "182") (name "unconnected-(U2D-IO_L22P_3-PadW5)") (class "Default")
      (node (ref "U2") (pin "W5") (pinfunction "IO_L22P_3_W5") (pintype "passive"))
    )
    (net (code "183") (name "unconnected-(U2D-IO_L23N_3-PadU7)") (class "Default")
      (node (ref "U2") (pin "U7") (pinfunction "IO_L23N_3_U7") (pintype "passive"))
    )
    (net (code "184") (name "unconnected-(U2D-IO_L23P_3-PadU8)") (class "Default")
      (node (ref "U2") (pin "U8") (pinfunction "IO_L23P_3_U8") (pintype "passive"))
    )
    (net (code "185") (name "unconnected-(U2D-IO_L24N_3-PadV5)") (class "Default")
      (node (ref "U2") (pin "V5") (pinfunction "IO_L24N_3_V5") (pintype "passive"))
    )
    (net (code "186") (name "unconnected-(U2D-IO_L24P_3-PadU5)") (class "Default")
      (node (ref "U2") (pin "U5") (pinfunction "IO_L24P_3_U5") (pintype "passive"))
    )
    (net (code "187") (name "unconnected-(U2D-IO_L25N_3-PadU9)") (class "Default")
      (node (ref "U2") (pin "U9") (pinfunction "IO_L25N_3_U9") (pintype "passive"))
    )
    (net (code "188") (name "unconnected-(U2D-IO_L25P_3-PadT10)") (class "Default")
      (node (ref "U2") (pin "T10") (pinfunction "IO_L25P_3_T10") (pintype "passive"))
    )
    (net (code "189") (name "unconnected-(U2D-IO_L27N_3-PadT9)") (class "Default")
      (node (ref "U2") (pin "T9") (pinfunction "IO_L27N_3_T9") (pintype "passive"))
    )
    (net (code "190") (name "unconnected-(U2D-IO_L27P_3-PadR10)") (class "Default")
      (node (ref "U2") (pin "R10") (pinfunction "IO_L27P_3_R10") (pintype "passive"))
    )
    (net (code "191") (name "unconnected-(U2D-IO_L28N_3-PadU3)") (class "Default")
      (node (ref "U2") (pin "U3") (pinfunction "IO_L28N_3_U3") (pintype "passive"))
    )
    (net (code "192") (name "unconnected-(U2D-IO_L28P_3-PadU4)") (class "Default")
      (node (ref "U2") (pin "U4") (pinfunction "IO_L28P_3_U4") (pintype "passive"))
    )
    (net (code "193") (name "unconnected-(U2D-IO_L29N_3-PadT6)") (class "Default")
      (node (ref "U2") (pin "T6") (pinfunction "IO_L29N_3_T6") (pintype "passive"))
    )
    (net (code "194") (name "unconnected-(U2D-IO_L29P_3-PadT8)") (class "Default")
      (node (ref "U2") (pin "T8") (pinfunction "IO_L29P_3_T8") (pintype "passive"))
    )
    (net (code "195") (name "unconnected-(U2D-IO_L30N_3-PadT4)") (class "Default")
      (node (ref "U2") (pin "T4") (pinfunction "IO_L30N_3_T4") (pintype "passive"))
    )
    (net (code "196") (name "unconnected-(U2D-IO_L30P_3-PadR5)") (class "Default")
      (node (ref "U2") (pin "R5") (pinfunction "IO_L30P_3_R5") (pintype "passive"))
    )
    (net (code "197") (name "unconnected-(U2D-IO_L31P_3-PadR7)") (class "Default")
      (node (ref "U2") (pin "R7") (pinfunction "IO_L31P_3_R7") (pintype "passive"))
    )
    (net (code "198") (name "unconnected-(U2D-IO_L55N_M3A14_3-PadM4)") (class "Default")
      (node (ref "U2") (pin "M4") (pinfunction "IO_L55N_M3A14_3_M4") (pintype "passive"))
    )
  )
)
